# design.net
KiCad netlist of a schematic drawn in Altium Designer
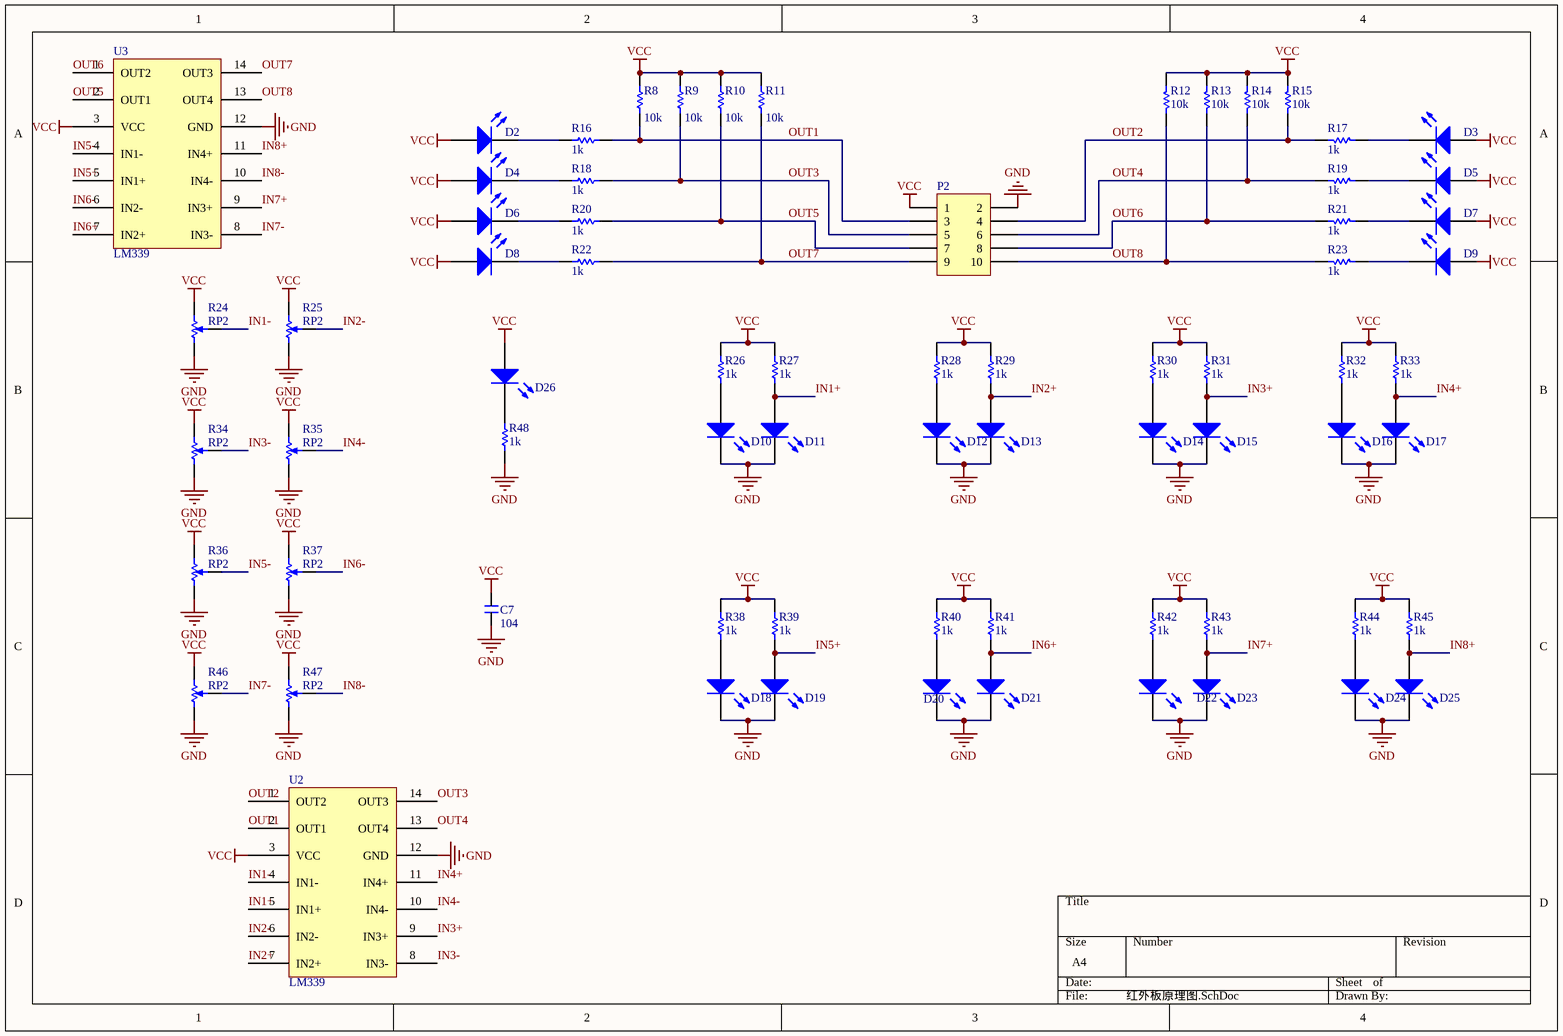
[diagram p0: 红外板原理图.SchDoc]

(export (version "E")
  (design (tool "Eeschema 10.0.6"))
  (components
    (comp (ref "C7")
      (value "CAP")
      (footprint "RAD-0.1")
      (description "无极性")
      (fields (field (name "ALTIUM_UNNAMED_1") "104"))
      (libsource (lib "1阻容电感元件") (part "CAP"))
    )
    (comp (ref "D2")
      (value "LED4")
      (footprint "LED1")
      (description "0603")
      (libsource (lib "2二极管三极管") (part "LED4"))
    )
    (comp (ref "D3")
      (value "LED4")
      (footprint "LED1")
      (description "0603")
      (libsource (lib "2二极管三极管") (part "LED4"))
    )
    (comp (ref "D4")
      (value "LED4")
      (footprint "LED1")
      (description "0603")
      (libsource (lib "2二极管三极管") (part "LED4"))
    )
    (comp (ref "D5")
      (value "LED4")
      (footprint "LED1")
      (description "0603")
      (libsource (lib "2二极管三极管") (part "LED4"))
    )
    (comp (ref "D6")
      (value "LED4")
      (footprint "LED1")
      (description "0603")
      (libsource (lib "2二极管三极管") (part "LED4"))
    )
    (comp (ref "D7")
      (value "LED4")
      (footprint "LED1")
      (description "0603")
      (libsource (lib "2二极管三极管") (part "LED4"))
    )
    (comp (ref "D8")
      (value "LED4")
      (footprint "LED1")
      (description "0603")
      (libsource (lib "2二极管三极管") (part "LED4"))
    )
    (comp (ref "D9")
      (value "LED4")
      (footprint "LED1")
      (description "0603")
      (libsource (lib "2二极管三极管") (part "LED4"))
    )
    (comp (ref "D10")
      (value "LED4")
      (footprint "LED1")
      (description "0603")
      (libsource (lib "2二极管三极管") (part "LED4"))
    )
    (comp (ref "D11")
      (value "LED4")
      (footprint "LED1")
      (description "0603")
      (libsource (lib "2二极管三极管") (part "LED4"))
    )
    (comp (ref "D12")
      (value "LED4")
      (footprint "LED1")
      (description "0603")
      (libsource (lib "2二极管三极管") (part "LED4"))
    )
    (comp (ref "D13")
      (value "LED4")
      (footprint "LED1")
      (description "0603")
      (libsource (lib "2二极管三极管") (part "LED4"))
    )
    (comp (ref "D14")
      (value "LED4")
      (footprint "LED1")
      (description "0603")
      (libsource (lib "2二极管三极管") (part "LED4"))
    )
    (comp (ref "D15")
      (value "LED4")
      (footprint "LED1")
      (description "0603")
      (libsource (lib "2二极管三极管") (part "LED4"))
    )
    (comp (ref "D16")
      (value "LED4")
      (footprint "LED1")
      (description "0603")
      (libsource (lib "2二极管三极管") (part "LED4"))
    )
    (comp (ref "D17")
      (value "LED4")
      (footprint "LED1")
      (description "0603")
      (libsource (lib "2二极管三极管") (part "LED4"))
    )
    (comp (ref "D18")
      (value "LED4")
      (footprint "LED1")
      (description "0603")
      (libsource (lib "2二极管三极管") (part "LED4"))
    )
    (comp (ref "D19")
      (value "LED4")
      (footprint "LED1")
      (description "0603")
      (libsource (lib "2二极管三极管") (part "LED4"))
    )
    (comp (ref "D20")
      (value "LED4")
      (footprint "LED1")
      (description "0603")
      (libsource (lib "2二极管三极管") (part "LED4"))
    )
    (comp (ref "D21")
      (value "LED4")
      (footprint "LED1")
      (description "0603")
      (libsource (lib "2二极管三极管") (part "LED4"))
    )
    (comp (ref "D22")
      (value "LED4")
      (footprint "LED1")
      (description "0603")
      (libsource (lib "2二极管三极管") (part "LED4"))
    )
    (comp (ref "D23")
      (value "LED4")
      (footprint "LED1")
      (description "0603")
      (libsource (lib "2二极管三极管") (part "LED4"))
    )
    (comp (ref "D24")
      (value "LED4")
      (footprint "LED1")
      (description "0603")
      (libsource (lib "2二极管三极管") (part "LED4"))
    )
    (comp (ref "D25")
      (value "LED4")
      (footprint "LED1")
      (description "0603")
      (libsource (lib "2二极管三极管") (part "LED4"))
    )
    (comp (ref "D26")
      (value "LED4")
      (footprint "LED1")
      (description "0603")
      (libsource (lib "2二极管三极管") (part "LED4"))
    )
    (comp (ref "P2")
      (value "Header 5X2")
      (footprint "HDR2X5")
      (description "Header, 5-Pin, Dual row")
      (fields (field (name "PUBLISHER") "Altium Limited"))
      (libsource (lib "01 Connect_IntegratedLibrary") (part "Header 5X2"))
    )
    (comp (ref "R8")
      (value "10k")
      (footprint "AXIAL-0.4")
      (description "Resistor")
      (fields (field (name "Comment") "Res1") (field (name "PUBLISHER") "Altium Limited"))
      (libsource (lib "Miscellaneous Devices") (part "Res1"))
    )
    (comp (ref "R9")
      (value "10k")
      (footprint "AXIAL-0.4")
      (description "Resistor")
      (fields (field (name "Comment") "Res1") (field (name "PUBLISHER") "Altium Limited"))
      (libsource (lib "Miscellaneous Devices") (part "Res1"))
    )
    (comp (ref "R10")
      (value "10k")
      (footprint "AXIAL-0.4")
      (description "Resistor")
      (fields (field (name "Comment") "Res1") (field (name "PUBLISHER") "Altium Limited"))
      (libsource (lib "Miscellaneous Devices") (part "Res1"))
    )
    (comp (ref "R11")
      (value "10k")
      (footprint "AXIAL-0.4")
      (description "Resistor")
      (fields (field (name "Comment") "Res1") (field (name "PUBLISHER") "Altium Limited"))
      (libsource (lib "Miscellaneous Devices") (part "Res1"))
    )
    (comp (ref "R12")
      (value "10k")
      (footprint "AXIAL-0.4")
      (description "Resistor")
      (fields (field (name "Comment") "Res1") (field (name "PUBLISHER") "Altium Limited"))
      (libsource (lib "Miscellaneous Devices") (part "Res1"))
    )
    (comp (ref "R13")
      (value "10k")
      (footprint "AXIAL-0.4")
      (description "Resistor")
      (fields (field (name "Comment") "Res1") (field (name "PUBLISHER") "Altium Limited"))
      (libsource (lib "Miscellaneous Devices") (part "Res1"))
    )
    (comp (ref "R14")
      (value "10k")
      (footprint "AXIAL-0.4")
      (description "Resistor")
      (fields (field (name "Comment") "Res1") (field (name "PUBLISHER") "Altium Limited"))
      (libsource (lib "Miscellaneous Devices") (part "Res1"))
    )
    (comp (ref "R15")
      (value "10k")
      (footprint "AXIAL-0.4")
      (description "Resistor")
      (fields (field (name "Comment") "Res1") (field (name "PUBLISHER") "Altium Limited"))
      (libsource (lib "Miscellaneous Devices") (part "Res1"))
    )
    (comp (ref "R16")
      (value "1k")
      (footprint "AXIAL-0.4")
      (description "Resistor")
      (fields (field (name "Comment") "Res1") (field (name "PUBLISHER") "Altium Limited"))
      (libsource (lib "Miscellaneous Devices") (part "Res1"))
    )
    (comp (ref "R17")
      (value "1k")
      (footprint "AXIAL-0.4")
      (description "Resistor")
      (fields (field (name "Comment") "Res1") (field (name "PUBLISHER") "Altium Limited"))
      (libsource (lib "Miscellaneous Devices") (part "Res1"))
    )
    (comp (ref "R18")
      (value "1k")
      (footprint "AXIAL-0.4")
      (description "Resistor")
      (fields (field (name "Comment") "Res1") (field (name "PUBLISHER") "Altium Limited"))
      (libsource (lib "Miscellaneous Devices") (part "Res1"))
    )
    (comp (ref "R19")
      (value "1k")
      (footprint "AXIAL-0.4")
      (description "Resistor")
      (fields (field (name "Comment") "Res1") (field (name "PUBLISHER") "Altium Limited"))
      (libsource (lib "Miscellaneous Devices") (part "Res1"))
    )
    (comp (ref "R20")
      (value "1k")
      (footprint "AXIAL-0.4")
      (description "Resistor")
      (fields (field (name "Comment") "Res1") (field (name "PUBLISHER") "Altium Limited"))
      (libsource (lib "Miscellaneous Devices") (part "Res1"))
    )
    (comp (ref "R21")
      (value "1k")
      (footprint "AXIAL-0.4")
      (description "Resistor")
      (fields (field (name "Comment") "Res1") (field (name "PUBLISHER") "Altium Limited"))
      (libsource (lib "Miscellaneous Devices") (part "Res1"))
    )
    (comp (ref "R22")
      (value "1k")
      (footprint "AXIAL-0.4")
      (description "Resistor")
      (fields (field (name "Comment") "Res1") (field (name "PUBLISHER") "Altium Limited"))
      (libsource (lib "Miscellaneous Devices") (part "Res1"))
    )
    (comp (ref "R23")
      (value "1k")
      (footprint "AXIAL-0.4")
      (description "Resistor")
      (fields (field (name "Comment") "Res1") (field (name "PUBLISHER") "Altium Limited"))
      (libsource (lib "Miscellaneous Devices") (part "Res1"))
    )
    (comp (ref "R24")
      (value "RP2")
      (footprint "POT SMALL")
      (description "Square Trimming Potentiometer")
      (fields (field (name "PUBLISHER") "Altium Limited"))
      (libsource (lib "Miscellaneous Devices") (part "RPot SM"))
    )
    (comp (ref "R25")
      (value "RP2")
      (footprint "POT SMALL")
      (description "Square Trimming Potentiometer")
      (fields (field (name "PUBLISHER") "Altium Limited"))
      (libsource (lib "Miscellaneous Devices") (part "RPot SM"))
    )
    (comp (ref "R26")
      (value "1k")
      (footprint "AXIAL-0.4")
      (description "Resistor")
      (fields (field (name "Comment") "Res1") (field (name "PUBLISHER") "Altium Limited"))
      (libsource (lib "Miscellaneous Devices") (part "Res1"))
    )
    (comp (ref "R27")
      (value "1k")
      (footprint "AXIAL-0.4")
      (description "Resistor")
      (fields (field (name "Comment") "Res1") (field (name "PUBLISHER") "Altium Limited"))
      (libsource (lib "Miscellaneous Devices") (part "Res1"))
    )
    (comp (ref "R28")
      (value "1k")
      (footprint "AXIAL-0.4")
      (description "Resistor")
      (fields (field (name "Comment") "Res1") (field (name "PUBLISHER") "Altium Limited"))
      (libsource (lib "Miscellaneous Devices") (part "Res1"))
    )
    (comp (ref "R29")
      (value "1k")
      (footprint "AXIAL-0.4")
      (description "Resistor")
      (fields (field (name "Comment") "Res1") (field (name "PUBLISHER") "Altium Limited"))
      (libsource (lib "Miscellaneous Devices") (part "Res1"))
    )
    (comp (ref "R30")
      (value "1k")
      (footprint "AXIAL-0.4")
      (description "Resistor")
      (fields (field (name "Comment") "Res1") (field (name "PUBLISHER") "Altium Limited"))
      (libsource (lib "Miscellaneous Devices") (part "Res1"))
    )
    (comp (ref "R31")
      (value "1k")
      (footprint "AXIAL-0.4")
      (description "Resistor")
      (fields (field (name "Comment") "Res1") (field (name "PUBLISHER") "Altium Limited"))
      (libsource (lib "Miscellaneous Devices") (part "Res1"))
    )
    (comp (ref "R32")
      (value "1k")
      (footprint "AXIAL-0.4")
      (description "Resistor")
      (fields (field (name "Comment") "Res1") (field (name "PUBLISHER") "Altium Limited"))
      (libsource (lib "Miscellaneous Devices") (part "Res1"))
    )
    (comp (ref "R33")
      (value "1k")
      (footprint "AXIAL-0.4")
      (description "Resistor")
      (fields (field (name "Comment") "Res1") (field (name "PUBLISHER") "Altium Limited"))
      (libsource (lib "Miscellaneous Devices") (part "Res1"))
    )
    (comp (ref "R34")
      (value "RP2")
      (footprint "POT SMALL")
      (description "Square Trimming Potentiometer")
      (fields (field (name "PUBLISHER") "Altium Limited"))
      (libsource (lib "Miscellaneous Devices") (part "RPot SM"))
    )
    (comp (ref "R35")
      (value "RP2")
      (footprint "POT SMALL")
      (description "Square Trimming Potentiometer")
      (fields (field (name "PUBLISHER") "Altium Limited"))
      (libsource (lib "Miscellaneous Devices") (part "RPot SM"))
    )
    (comp (ref "R36")
      (value "RP2")
      (footprint "POT SMALL")
      (description "Square Trimming Potentiometer")
      (fields (field (name "PUBLISHER") "Altium Limited"))
      (libsource (lib "Miscellaneous Devices") (part "RPot SM"))
    )
    (comp (ref "R37")
      (value "RP2")
      (footprint "POT SMALL")
      (description "Square Trimming Potentiometer")
      (fields (field (name "PUBLISHER") "Altium Limited"))
      (libsource (lib "Miscellaneous Devices") (part "RPot SM"))
    )
    (comp (ref "R38")
      (value "1k")
      (footprint "AXIAL-0.4")
      (description "Resistor")
      (fields (field (name "Comment") "Res1") (field (name "PUBLISHER") "Altium Limited"))
      (libsource (lib "Miscellaneous Devices") (part "Res1"))
    )
    (comp (ref "R39")
      (value "1k")
      (footprint "AXIAL-0.4")
      (description "Resistor")
      (fields (field (name "Comment") "Res1") (field (name "PUBLISHER") "Altium Limited"))
      (libsource (lib "Miscellaneous Devices") (part "Res1"))
    )
    (comp (ref "R40")
      (value "1k")
      (footprint "AXIAL-0.4")
      (description "Resistor")
      (fields (field (name "Comment") "Res1") (field (name "PUBLISHER") "Altium Limited"))
      (libsource (lib "Miscellaneous Devices") (part "Res1"))
    )
    (comp (ref "R41")
      (value "1k")
      (footprint "AXIAL-0.4")
      (description "Resistor")
      (fields (field (name "Comment") "Res1") (field (name "PUBLISHER") "Altium Limited"))
      (libsource (lib "Miscellaneous Devices") (part "Res1"))
    )
    (comp (ref "R42")
      (value "1k")
      (footprint "AXIAL-0.4")
      (description "Resistor")
      (fields (field (name "Comment") "Res1") (field (name "PUBLISHER") "Altium Limited"))
      (libsource (lib "Miscellaneous Devices") (part "Res1"))
    )
    (comp (ref "R43")
      (value "1k")
      (footprint "AXIAL-0.4")
      (description "Resistor")
      (fields (field (name "Comment") "Res1") (field (name "PUBLISHER") "Altium Limited"))
      (libsource (lib "Miscellaneous Devices") (part "Res1"))
    )
    (comp (ref "R44")
      (value "1k")
      (footprint "AXIAL-0.4")
      (description "Resistor")
      (fields (field (name "Comment") "Res1") (field (name "PUBLISHER") "Altium Limited"))
      (libsource (lib "Miscellaneous Devices") (part "Res1"))
    )
    (comp (ref "R45")
      (value "1k")
      (footprint "AXIAL-0.4")
      (description "Resistor")
      (fields (field (name "Comment") "Res1") (field (name "PUBLISHER") "Altium Limited"))
      (libsource (lib "Miscellaneous Devices") (part "Res1"))
    )
    (comp (ref "R46")
      (value "RP2")
      (footprint "POT SMALL")
      (description "Square Trimming Potentiometer")
      (fields (field (name "PUBLISHER") "Altium Limited"))
      (libsource (lib "Miscellaneous Devices") (part "RPot SM"))
    )
    (comp (ref "R47")
      (value "RP2")
      (footprint "POT SMALL")
      (description "Square Trimming Potentiometer")
      (fields (field (name "PUBLISHER") "Altium Limited"))
      (libsource (lib "Miscellaneous Devices") (part "RPot SM"))
    )
    (comp (ref "R48")
      (value "1k")
      (footprint "AXIAL-0.4")
      (description "Resistor")
      (fields (field (name "Comment") "Res1") (field (name "PUBLISHER") "Altium Limited"))
      (libsource (lib "Miscellaneous Devices") (part "Res1"))
    )
    (comp (ref "U2") (value "LM339") (libsource (lib "Schlib1") (part "LM339")))
    (comp (ref "U3") (value "LM339") (libsource (lib "Schlib1") (part "LM339")))
  )
  (nets
    (net (code "1") (name "/IN1+") (class "Default")
      (node (ref "D11") (pin "1") (pinfunction "A_1") (pintype "passive"))
      (node (ref "R27") (pin "2") (pinfunction "2_2") (pintype "passive"))
      (node (ref "U2") (pin "5") (pinfunction "IN1+_5") (pintype "passive"))
    )
    (net (code "2") (name "/IN1-") (class "Default")
      (node (ref "R24") (pin "W") (pinfunction "W_W") (pintype "passive"))
      (node (ref "U2") (pin "4") (pinfunction "IN1-_4") (pintype "passive"))
    )
    (net (code "3") (name "/IN2+") (class "Default")
      (node (ref "D13") (pin "1") (pinfunction "A_1") (pintype "passive"))
      (node (ref "R29") (pin "2") (pinfunction "2_2") (pintype "passive"))
      (node (ref "U2") (pin "7") (pinfunction "IN2+_7") (pintype "passive"))
    )
    (net (code "4") (name "/IN2-") (class "Default")
      (node (ref "R25") (pin "W") (pinfunction "W_W") (pintype "passive"))
      (node (ref "U2") (pin "6") (pinfunction "IN2-_6") (pintype "passive"))
    )
    (net (code "5") (name "/IN3+") (class "Default")
      (node (ref "D15") (pin "1") (pinfunction "A_1") (pintype "passive"))
      (node (ref "R31") (pin "2") (pinfunction "2_2") (pintype "passive"))
      (node (ref "U2") (pin "9") (pinfunction "IN3+_9") (pintype "passive"))
    )
    (net (code "6") (name "/IN3-") (class "Default")
      (node (ref "R34") (pin "W") (pinfunction "W_W") (pintype "passive"))
      (node (ref "U2") (pin "8") (pinfunction "IN3-_8") (pintype "passive"))
    )
    (net (code "7") (name "/IN4+") (class "Default")
      (node (ref "D17") (pin "1") (pinfunction "A_1") (pintype "passive"))
      (node (ref "R33") (pin "2") (pinfunction "2_2") (pintype "passive"))
      (node (ref "U2") (pin "11") (pinfunction "IN4+_11") (pintype "passive"))
    )
    (net (code "8") (name "/IN4-") (class "Default")
      (node (ref "R35") (pin "W") (pinfunction "W_W") (pintype "passive"))
      (node (ref "U2") (pin "10") (pinfunction "IN4-_10") (pintype "passive"))
    )
    (net (code "9") (name "/IN5+") (class "Default")
      (node (ref "D19") (pin "1") (pinfunction "A_1") (pintype "passive"))
      (node (ref "R39") (pin "2") (pinfunction "2_2") (pintype "passive"))
      (node (ref "U3") (pin "5") (pinfunction "IN1+_5") (pintype "passive"))
    )
    (net (code "10") (name "/IN5-") (class "Default")
      (node (ref "R36") (pin "W") (pinfunction "W_W") (pintype "passive"))
      (node (ref "U3") (pin "4") (pinfunction "IN1-_4") (pintype "passive"))
    )
    (net (code "11") (name "/IN6+") (class "Default")
      (node (ref "D21") (pin "1") (pinfunction "A_1") (pintype "passive"))
      (node (ref "R41") (pin "2") (pinfunction "2_2") (pintype "passive"))
      (node (ref "U3") (pin "7") (pinfunction "IN2+_7") (pintype "passive"))
    )
    (net (code "12") (name "/IN6-") (class "Default")
      (node (ref "R37") (pin "W") (pinfunction "W_W") (pintype "passive"))
      (node (ref "U3") (pin "6") (pinfunction "IN2-_6") (pintype "passive"))
    )
    (net (code "13") (name "/IN7+") (class "Default")
      (node (ref "D23") (pin "1") (pinfunction "A_1") (pintype "passive"))
      (node (ref "R43") (pin "2") (pinfunction "2_2") (pintype "passive"))
      (node (ref "U3") (pin "9") (pinfunction "IN3+_9") (pintype "passive"))
    )
    (net (code "14") (name "/IN7-") (class "Default")
      (node (ref "R46") (pin "W") (pinfunction "W_W") (pintype "passive"))
      (node (ref "U3") (pin "8") (pinfunction "IN3-_8") (pintype "passive"))
    )
    (net (code "15") (name "/IN8+") (class "Default")
      (node (ref "D25") (pin "1") (pinfunction "A_1") (pintype "passive"))
      (node (ref "R45") (pin "2") (pinfunction "2_2") (pintype "passive"))
      (node (ref "U3") (pin "11") (pinfunction "IN4+_11") (pintype "passive"))
    )
    (net (code "16") (name "/IN8-") (class "Default")
      (node (ref "R47") (pin "W") (pinfunction "W_W") (pintype "passive"))
      (node (ref "U3") (pin "10") (pinfunction "IN4-_10") (pintype "passive"))
    )
    (net (code "17") (name "/OUT1") (class "Default")
      (node (ref "P2") (pin "3") (pinfunction "3_3") (pintype "passive"))
      (node (ref "R16") (pin "1") (pinfunction "1_1") (pintype "passive"))
      (node (ref "R8") (pin "1") (pinfunction "1_1") (pintype "passive"))
      (node (ref "U2") (pin "2") (pinfunction "OUT1_2") (pintype "passive"))
    )
    (net (code "18") (name "/OUT2") (class "Default")
      (node (ref "P2") (pin "4") (pinfunction "4_4") (pintype "passive"))
      (node (ref "R15") (pin "1") (pinfunction "1_1") (pintype "passive"))
      (node (ref "R17") (pin "1") (pinfunction "1_1") (pintype "passive"))
      (node (ref "U2") (pin "1") (pinfunction "OUT2_1") (pintype "passive"))
    )
    (net (code "19") (name "/OUT3") (class "Default")
      (node (ref "P2") (pin "5") (pinfunction "5_5") (pintype "passive"))
      (node (ref "R18") (pin "1") (pinfunction "1_1") (pintype "passive"))
      (node (ref "R9") (pin "1") (pinfunction "1_1") (pintype "passive"))
      (node (ref "U2") (pin "14") (pinfunction "OUT3_14") (pintype "passive"))
    )
    (net (code "20") (name "/OUT4") (class "Default")
      (node (ref "P2") (pin "6") (pinfunction "6_6") (pintype "passive"))
      (node (ref "R14") (pin "1") (pinfunction "1_1") (pintype "passive"))
      (node (ref "R19") (pin "1") (pinfunction "1_1") (pintype "passive"))
      (node (ref "U2") (pin "13") (pinfunction "OUT4_13") (pintype "passive"))
    )
    (net (code "21") (name "/OUT5") (class "Default")
      (node (ref "P2") (pin "7") (pinfunction "7_7") (pintype "passive"))
      (node (ref "R10") (pin "1") (pinfunction "1_1") (pintype "passive"))
      (node (ref "R20") (pin "1") (pinfunction "1_1") (pintype "passive"))
      (node (ref "U3") (pin "2") (pinfunction "OUT1_2") (pintype "passive"))
    )
    (net (code "22") (name "/OUT6") (class "Default")
      (node (ref "P2") (pin "8") (pinfunction "8_8") (pintype "passive"))
      (node (ref "R13") (pin "1") (pinfunction "1_1") (pintype "passive"))
      (node (ref "R21") (pin "1") (pinfunction "1_1") (pintype "passive"))
      (node (ref "U3") (pin "1") (pinfunction "OUT2_1") (pintype "passive"))
    )
    (net (code "23") (name "/OUT7") (class "Default")
      (node (ref "P2") (pin "9") (pinfunction "9_9") (pintype "passive"))
      (node (ref "R11") (pin "1") (pinfunction "1_1") (pintype "passive"))
      (node (ref "R22") (pin "1") (pinfunction "1_1") (pintype "passive"))
      (node (ref "U3") (pin "14") (pinfunction "OUT3_14") (pintype "passive"))
    )
    (net (code "24") (name "/OUT8") (class "Default")
      (node (ref "P2") (pin "10") (pinfunction "10_10") (pintype "passive"))
      (node (ref "R12") (pin "1") (pinfunction "1_1") (pintype "passive"))
      (node (ref "R23") (pin "1") (pinfunction "1_1") (pintype "passive"))
      (node (ref "U3") (pin "13") (pinfunction "OUT4_13") (pintype "passive"))
    )
    (net (code "25") (name "GND") (class "Default")
      (node (ref "C7") (pin "2") (pinfunction "2_2") (pintype "passive"))
      (node (ref "D10") (pin "2") (pinfunction "K_2") (pintype "passive"))
      (node (ref "D11") (pin "2") (pinfunction "K_2") (pintype "passive"))
      (node (ref "D12") (pin "2") (pinfunction "K_2") (pintype "passive"))
      (node (ref "D13") (pin "2") (pinfunction "K_2") (pintype "passive"))
      (node (ref "D14") (pin "2") (pinfunction "K_2") (pintype "passive"))
      (node (ref "D15") (pin "2") (pinfunction "K_2") (pintype "passive"))
      (node (ref "D16") (pin "2") (pinfunction "K_2") (pintype "passive"))
      (node (ref "D17") (pin "2") (pinfunction "K_2") (pintype "passive"))
      (node (ref "D18") (pin "2") (pinfunction "K_2") (pintype "passive"))
      (node (ref "D19") (pin "2") (pinfunction "K_2") (pintype "passive"))
      (node (ref "D20") (pin "2") (pinfunction "K_2") (pintype "passive"))
      (node (ref "D21") (pin "2") (pinfunction "K_2") (pintype "passive"))
      (node (ref "D22") (pin "2") (pinfunction "K_2") (pintype "passive"))
      (node (ref "D23") (pin "2") (pinfunction "K_2") (pintype "passive"))
      (node (ref "D24") (pin "2") (pinfunction "K_2") (pintype "passive"))
      (node (ref "D25") (pin "2") (pinfunction "K_2") (pintype "passive"))
      (node (ref "P2") (pin "2") (pinfunction "2_2") (pintype "passive"))
      (node (ref "R24") (pin "CCW") (pinfunction "-_CCW") (pintype "passive"))
      (node (ref "R25") (pin "CCW") (pinfunction "-_CCW") (pintype "passive"))
      (node (ref "R34") (pin "CCW") (pinfunction "-_CCW") (pintype "passive"))
      (node (ref "R35") (pin "CCW") (pinfunction "-_CCW") (pintype "passive"))
      (node (ref "R36") (pin "CCW") (pinfunction "-_CCW") (pintype "passive"))
      (node (ref "R37") (pin "CCW") (pinfunction "-_CCW") (pintype "passive"))
      (node (ref "R46") (pin "CCW") (pinfunction "-_CCW") (pintype "passive"))
      (node (ref "R47") (pin "CCW") (pinfunction "-_CCW") (pintype "passive"))
      (node (ref "R48") (pin "2") (pinfunction "2_2") (pintype "passive"))
      (node (ref "U2") (pin "12") (pinfunction "GND_12") (pintype "passive"))
      (node (ref "U3") (pin "12") (pinfunction "GND_12") (pintype "passive"))
    )
    (net (code "26") (name "Net-(D2-K)") (class "Default")
      (node (ref "D2") (pin "2") (pinfunction "K_2") (pintype "passive"))
      (node (ref "R16") (pin "2") (pinfunction "2_2") (pintype "passive"))
    )
    (net (code "27") (name "Net-(D3-K)") (class "Default")
      (node (ref "D3") (pin "2") (pinfunction "K_2") (pintype "passive"))
      (node (ref "R17") (pin "2") (pinfunction "2_2") (pintype "passive"))
    )
    (net (code "28") (name "Net-(D4-K)") (class "Default")
      (node (ref "D4") (pin "2") (pinfunction "K_2") (pintype "passive"))
      (node (ref "R18") (pin "2") (pinfunction "2_2") (pintype "passive"))
    )
    (net (code "29") (name "Net-(D5-K)") (class "Default")
      (node (ref "D5") (pin "2") (pinfunction "K_2") (pintype "passive"))
      (node (ref "R19") (pin "2") (pinfunction "2_2") (pintype "passive"))
    )
    (net (code "30") (name "Net-(D6-K)") (class "Default")
      (node (ref "D6") (pin "2") (pinfunction "K_2") (pintype "passive"))
      (node (ref "R20") (pin "2") (pinfunction "2_2") (pintype "passive"))
    )
    (net (code "31") (name "Net-(D7-K)") (class "Default")
      (node (ref "D7") (pin "2") (pinfunction "K_2") (pintype "passive"))
      (node (ref "R21") (pin "2") (pinfunction "2_2") (pintype "passive"))
    )
    (net (code "32") (name "Net-(D8-K)") (class "Default")
      (node (ref "D8") (pin "2") (pinfunction "K_2") (pintype "passive"))
      (node (ref "R22") (pin "2") (pinfunction "2_2") (pintype "passive"))
    )
    (net (code "33") (name "Net-(D9-K)") (class "Default")
      (node (ref "D9") (pin "2") (pinfunction "K_2") (pintype "passive"))
      (node (ref "R23") (pin "2") (pinfunction "2_2") (pintype "passive"))
    )
    (net (code "34") (name "Net-(D10-A)") (class "Default")
      (node (ref "D10") (pin "1") (pinfunction "A_1") (pintype "passive"))
      (node (ref "R26") (pin "2") (pinfunction "2_2") (pintype "passive"))
    )
    (net (code "35") (name "Net-(D12-A)") (class "Default")
      (node (ref "D12") (pin "1") (pinfunction "A_1") (pintype "passive"))
      (node (ref "R28") (pin "2") (pinfunction "2_2") (pintype "passive"))
    )
    (net (code "36") (name "Net-(D14-A)") (class "Default")
      (node (ref "D14") (pin "1") (pinfunction "A_1") (pintype "passive"))
      (node (ref "R30") (pin "2") (pinfunction "2_2") (pintype "passive"))
    )
    (net (code "37") (name "Net-(D16-A)") (class "Default")
      (node (ref "D16") (pin "1") (pinfunction "A_1") (pintype "passive"))
      (node (ref "R32") (pin "2") (pinfunction "2_2") (pintype "passive"))
    )
    (net (code "38") (name "Net-(D18-A)") (class "Default")
      (node (ref "D18") (pin "1") (pinfunction "A_1") (pintype "passive"))
      (node (ref "R38") (pin "2") (pinfunction "2_2") (pintype "passive"))
    )
    (net (code "39") (name "Net-(D20-A)") (class "Default")
      (node (ref "D20") (pin "1") (pinfunction "A_1") (pintype "passive"))
      (node (ref "R40") (pin "2") (pinfunction "2_2") (pintype "passive"))
    )
    (net (code "40") (name "Net-(D22-A)") (class "Default")
      (node (ref "D22") (pin "1") (pinfunction "A_1") (pintype "passive"))
      (node (ref "R42") (pin "2") (pinfunction "2_2") (pintype "passive"))
    )
    (net (code "41") (name "Net-(D24-A)") (class "Default")
      (node (ref "D24") (pin "1") (pinfunction "A_1") (pintype "passive"))
      (node (ref "R44") (pin "2") (pinfunction "2_2") (pintype "passive"))
    )
    (net (code "42") (name "Net-(D26-K)") (class "Default")
      (node (ref "D26") (pin "2") (pinfunction "K_2") (pintype "passive"))
      (node (ref "R48") (pin "1") (pinfunction "1_1") (pintype "passive"))
    )
    (net (code "43") (name "VCC") (class "Default")
      (node (ref "C7") (pin "1") (pinfunction "1_1") (pintype "passive"))
      (node (ref "D2") (pin "1") (pinfunction "A_1") (pintype "passive"))
      (node (ref "D26") (pin "1") (pinfunction "A_1") (pintype "passive"))
      (node (ref "D3") (pin "1") (pinfunction "A_1") (pintype "passive"))
      (node (ref "D4") (pin "1") (pinfunction "A_1") (pintype "passive"))
      (node (ref "D5") (pin "1") (pinfunction "A_1") (pintype "passive"))
      (node (ref "D6") (pin "1") (pinfunction "A_1") (pintype "passive"))
      (node (ref "D7") (pin "1") (pinfunction "A_1") (pintype "passive"))
      (node (ref "D8") (pin "1") (pinfunction "A_1") (pintype "passive"))
      (node (ref "D9") (pin "1") (pinfunction "A_1") (pintype "passive"))
      (node (ref "P2") (pin "1") (pinfunction "1_1") (pintype "passive"))
      (node (ref "R10") (pin "2") (pinfunction "2_2") (pintype "passive"))
      (node (ref "R11") (pin "2") (pinfunction "2_2") (pintype "passive"))
      (node (ref "R12") (pin "2") (pinfunction "2_2") (pintype "passive"))
      (node (ref "R13") (pin "2") (pinfunction "2_2") (pintype "passive"))
      (node (ref "R14") (pin "2") (pinfunction "2_2") (pintype "passive"))
      (node (ref "R15") (pin "2") (pinfunction "2_2") (pintype "passive"))
      (node (ref "R24") (pin "CW") (pinfunction "+_CW") (pintype "passive"))
      (node (ref "R25") (pin "CW") (pinfunction "+_CW") (pintype "passive"))
      (node (ref "R26") (pin "1") (pinfunction "1_1") (pintype "passive"))
      (node (ref "R27") (pin "1") (pinfunction "1_1") (pintype "passive"))
      (node (ref "R28") (pin "1") (pinfunction "1_1") (pintype "passive"))
      (node (ref "R29") (pin "1") (pinfunction "1_1") (pintype "passive"))
      (node (ref "R30") (pin "1") (pinfunction "1_1") (pintype "passive"))
      (node (ref "R31") (pin "1") (pinfunction "1_1") (pintype "passive"))
      (node (ref "R32") (pin "1") (pinfunction "1_1") (pintype "passive"))
      (node (ref "R33") (pin "1") (pinfunction "1_1") (pintype "passive"))
      (node (ref "R34") (pin "CW") (pinfunction "+_CW") (pintype "passive"))
      (node (ref "R35") (pin "CW") (pinfunction "+_CW") (pintype "passive"))
      (node (ref "R36") (pin "CW") (pinfunction "+_CW") (pintype "passive"))
      (node (ref "R37") (pin "CW") (pinfunction "+_CW") (pintype "passive"))
      (node (ref "R38") (pin "1") (pinfunction "1_1") (pintype "passive"))
      (node (ref "R39") (pin "1") (pinfunction "1_1") (pintype "passive"))
      (node (ref "R40") (pin "1") (pinfunction "1_1") (pintype "passive"))
      (node (ref "R41") (pin "1") (pinfunction "1_1") (pintype "passive"))
      (node (ref "R42") (pin "1") (pinfunction "1_1") (pintype "passive"))
      (node (ref "R43") (pin "1") (pinfunction "1_1") (pintype "passive"))
      (node (ref "R44") (pin "1") (pinfunction "1_1") (pintype "passive"))
      (node (ref "R45") (pin "1") (pinfunction "1_1") (pintype "passive"))
      (node (ref "R46") (pin "CW") (pinfunction "+_CW") (pintype "passive"))
      (node (ref "R47") (pin "CW") (pinfunction "+_CW") (pintype "passive"))
      (node (ref "R8") (pin "2") (pinfunction "2_2") (pintype "passive"))
      (node (ref "R9") (pin "2") (pinfunction "2_2") (pintype "passive"))
      (node (ref "U2") (pin "3") (pinfunction "VCC_3") (pintype "passive"))
      (node (ref "U3") (pin "3") (pinfunction "VCC_3") (pintype "passive"))
    )
  )
)
